# pirFadeDC.net
KiCad netlist of a schematic drawn in EAGLE
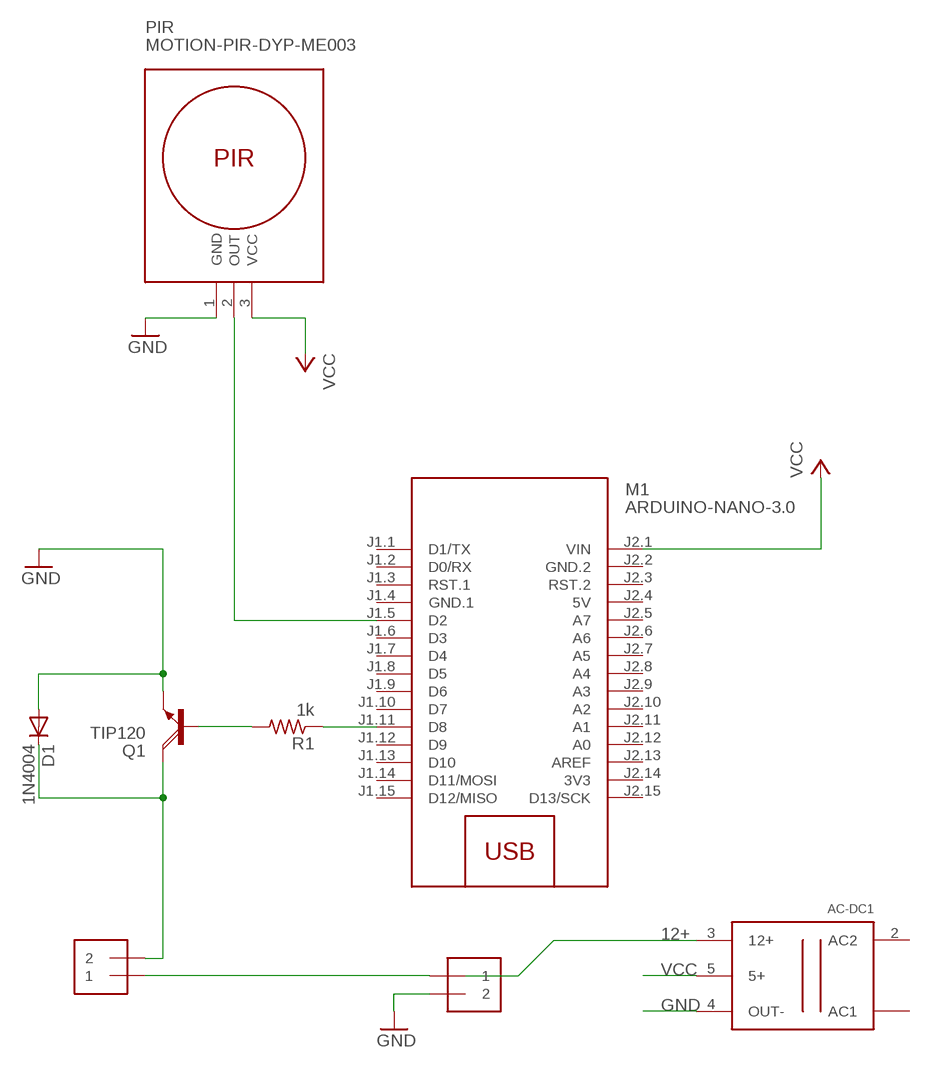
[diagram p0: schematic, sheet 1]

(export (version "E")
  (design (tool "Eeschema 10.0.6"))
  (components
    (comp (ref "AC-DC1")
      (value "GENERIC_AC/DC")
      (footprint "eagle-import:AC_DC")
      (libsource (lib "eagle-import") (part "GENERIC_AC/DC"))
    )
    (comp (ref "D1")
      (value "1N4004")
      (footprint "eagle-import:DO41-10")
      (libsource (lib "eagle-import") (part "1N4004"))
    )
    (comp (ref "J1")
      (value "1X2-3.5MM")
      (footprint "eagle-import:1X2-3.5MM")
      (libsource (lib "eagle-import") (part "1X2-3.5MM"))
    )
    (comp (ref "J2")
      (value "1X2-3.5MM")
      (footprint "eagle-import:1X2-3.5MM")
      (libsource (lib "eagle-import") (part "1X2-3.5MM"))
    )
    (comp (ref "M1")
      (value "ARDUINO-NANO-3.0")
      (footprint "eagle-import:ARDUINO-NANO-3.0")
      (libsource (lib "eagle-import") (part "ARDUINO-NANO-3.0"))
    )
    (comp (ref "PIR")
      (value "MOTION-PIR-DYP-ME003")
      (footprint "eagle-import:MOTION-PIR-DYP-ME003")
      (libsource (lib "eagle-import") (part "MOTION-PIR-DYP-ME003"))
    )
    (comp (ref "Q1")
      (value "TIP120")
      (footprint "eagle-import:TO220AH")
      (libsource (lib "eagle-import") (part "TIP120"))
    )
    (comp (ref "R1")
      (value "1k")
      (footprint "eagle-import:0805-THM")
      (libsource (lib "eagle-import") (part "FLIPFLOP-RES"))
    )
  )
  (nets
    (net (code "1") (name "/3V3") (class "Default")
      (node (ref "M1") (pin "J2.14") (pinfunction "3V3_J2.14") (pintype "power_in"))
    )
    (net (code "2") (name "/5V") (class "Default")
      (node (ref "M1") (pin "J2.4") (pinfunction "5V_J2.4") (pintype "power_in"))
    )
    (net (code "3") (name "/12+") (class "Default")
      (node (ref "AC-DC1") (pin "3") (pinfunction "12+_3") (pintype "output"))
    )
    (net (code "4") (name "/GND.1") (class "Default")
      (node (ref "M1") (pin "J1.4") (pinfunction "GND.1_J1.4") (pintype "power_in"))
    )
    (net (code "5") (name "/GND.2") (class "Default")
      (node (ref "M1") (pin "J2.2") (pinfunction "GND.2_J2.2") (pintype "power_in"))
    )
    (net (code "6") (name "GND") (class "Default")
      (node (ref "AC-DC1") (pin "4") (pinfunction "OUT-_4") (pintype "output"))
      (node (ref "D1") (pin "A") (pinfunction "A_A") (pintype "passive"))
      (node (ref "J2") (pin "2") (pinfunction "2_2") (pintype "passive"))
      (node (ref "PIR") (pin "1") (pinfunction "GND_1") (pintype "power_in"))
      (node (ref "Q1") (pin "E") (pinfunction "E_E") (pintype "passive"))
    )
    (net (code "7") (name "Net-(D1-PadC)") (class "Default")
      (node (ref "D1") (pin "C") (pinfunction "C_C") (pintype "passive"))
      (node (ref "J1") (pin "2") (pinfunction "2_2") (pintype "passive"))
      (node (ref "Q1") (pin "C") (pinfunction "C_C") (pintype "passive"))
    )
    (net (code "8") (name "Net-(J1-Pad1)") (class "Default")
      (node (ref "J1") (pin "1") (pinfunction "1_1") (pintype "passive"))
      (node (ref "J2") (pin "1") (pinfunction "1_1") (pintype "passive"))
    )
    (net (code "9") (name "Net-(M1-D2)") (class "Default")
      (node (ref "M1") (pin "J1.5") (pinfunction "D2_J1.5") (pintype "bidirectional"))
      (node (ref "PIR") (pin "2") (pinfunction "OUT_2") (pintype "output"))
    )
    (net (code "10") (name "Net-(M1-D8)") (class "Default")
      (node (ref "M1") (pin "J1.11") (pinfunction "D8_J1.11") (pintype "bidirectional"))
      (node (ref "R1") (pin "1") (pinfunction "1_1") (pintype "passive"))
    )
    (net (code "11") (name "Net-(Q1-PadB)") (class "Default")
      (node (ref "Q1") (pin "B") (pinfunction "B_B") (pintype "passive"))
      (node (ref "R1") (pin "2") (pinfunction "2_2") (pintype "passive"))
    )
    (net (code "12") (name "VCC") (class "Default")
      (node (ref "AC-DC1") (pin "5") (pinfunction "5+_5") (pintype "bidirectional"))
      (node (ref "M1") (pin "J2.1") (pinfunction "VIN_J2.1") (pintype "power_in"))
      (node (ref "PIR") (pin "3") (pinfunction "VCC_3") (pintype "power_in"))
    )
    (net (code "13") (name "unconnected-(AC-DC1-AC1-Pad1)") (class "Default")
      (node (ref "AC-DC1") (pin "1") (pinfunction "AC1_1") (pintype "input"))
    )
    (net (code "14") (name "unconnected-(AC-DC1-AC2-Pad2)") (class "Default")
      (node (ref "AC-DC1") (pin "2") (pinfunction "AC2_2") (pintype "input"))
    )
    (net (code "15") (name "unconnected-(M1-A0-PadJ2.12)") (class "Default")
      (node (ref "M1") (pin "J2.12") (pinfunction "A0_J2.12") (pintype "bidirectional"))
    )
    (net (code "16") (name "unconnected-(M1-A1-PadJ2.11)") (class "Default")
      (node (ref "M1") (pin "J2.11") (pinfunction "A1_J2.11") (pintype "bidirectional"))
    )
    (net (code "17") (name "unconnected-(M1-A2-PadJ2.10)") (class "Default")
      (node (ref "M1") (pin "J2.10") (pinfunction "A2_J2.10") (pintype "bidirectional"))
    )
    (net (code "18") (name "unconnected-(M1-A3-PadJ2.9)") (class "Default")
      (node (ref "M1") (pin "J2.9") (pinfunction "A3_J2.9") (pintype "bidirectional"))
    )
    (net (code "19") (name "unconnected-(M1-A4-PadJ2.8)") (class "Default")
      (node (ref "M1") (pin "J2.8") (pinfunction "A4_J2.8") (pintype "bidirectional"))
    )
    (net (code "20") (name "unconnected-(M1-A5-PadJ2.7)") (class "Default")
      (node (ref "M1") (pin "J2.7") (pinfunction "A5_J2.7") (pintype "bidirectional"))
    )
    (net (code "21") (name "unconnected-(M1-A6-PadJ2.6)") (class "Default")
      (node (ref "M1") (pin "J2.6") (pinfunction "A6_J2.6") (pintype "bidirectional"))
    )
    (net (code "22") (name "unconnected-(M1-A7-PadJ2.5)") (class "Default")
      (node (ref "M1") (pin "J2.5") (pinfunction "A7_J2.5") (pintype "bidirectional"))
    )
    (net (code "23") (name "unconnected-(M1-AREF-PadJ2.13)") (class "Default")
      (node (ref "M1") (pin "J2.13") (pinfunction "AREF_J2.13") (pintype "bidirectional"))
    )
    (net (code "24") (name "unconnected-(M1-D0{slash}RX-PadJ1.2)") (class "Default")
      (node (ref "M1") (pin "J1.2") (pinfunction "D0/RX_J1.2") (pintype "bidirectional"))
    )
    (net (code "25") (name "unconnected-(M1-D1{slash}TX-PadJ1.1)") (class "Default")
      (node (ref "M1") (pin "J1.1") (pinfunction "D1/TX_J1.1") (pintype "bidirectional"))
    )
    (net (code "26") (name "unconnected-(M1-D3-PadJ1.6)") (class "Default")
      (node (ref "M1") (pin "J1.6") (pinfunction "D3_J1.6") (pintype "bidirectional"))
    )
    (net (code "27") (name "unconnected-(M1-D4-PadJ1.7)") (class "Default")
      (node (ref "M1") (pin "J1.7") (pinfunction "D4_J1.7") (pintype "bidirectional"))
    )
    (net (code "28") (name "unconnected-(M1-D5-PadJ1.8)") (class "Default")
      (node (ref "M1") (pin "J1.8") (pinfunction "D5_J1.8") (pintype "bidirectional"))
    )
    (net (code "29") (name "unconnected-(M1-D6-PadJ1.9)") (class "Default")
      (node (ref "M1") (pin "J1.9") (pinfunction "D6_J1.9") (pintype "bidirectional"))
    )
    (net (code "30") (name "unconnected-(M1-D7-PadJ1.10)") (class "Default")
      (node (ref "M1") (pin "J1.10") (pinfunction "D7_J1.10") (pintype "bidirectional"))
    )
    (net (code "31") (name "unconnected-(M1-D9-PadJ1.12)") (class "Default")
      (node (ref "M1") (pin "J1.12") (pinfunction "D9_J1.12") (pintype "bidirectional"))
    )
    (net (code "32") (name "unconnected-(M1-D10-PadJ1.13)") (class "Default")
      (node (ref "M1") (pin "J1.13") (pinfunction "D10_J1.13") (pintype "bidirectional"))
    )
    (net (code "33") (name "unconnected-(M1-D11{slash}MOSI-PadJ1.14)") (class "Default")
      (node (ref "M1") (pin "J1.14") (pinfunction "D11/MOSI_J1.14") (pintype "bidirectional"))
    )
    (net (code "34") (name "unconnected-(M1-D12{slash}MISO-PadJ1.15)") (class "Default")
      (node (ref "M1") (pin "J1.15") (pinfunction "D12/MISO_J1.15") (pintype "bidirectional"))
    )
    (net (code "35") (name "unconnected-(M1-D13{slash}SCK-PadJ2.15)") (class "Default")
      (node (ref "M1") (pin "J2.15") (pinfunction "D13/SCK_J2.15") (pintype "bidirectional"))
    )
    (net (code "36") (name "unconnected-(M1-RST.1-PadJ1.3)") (class "Default")
      (node (ref "M1") (pin "J1.3") (pinfunction "RST.1_J1.3") (pintype "bidirectional"))
    )
    (net (code "37") (name "unconnected-(M1-RST.2-PadJ2.3)") (class "Default")
      (node (ref "M1") (pin "J2.3") (pinfunction "RST.2_J2.3") (pintype "bidirectional"))
    )
  )
)
